# PX4FMUv2_4_6_4.net
KiCad netlist of a schematic drawn in Altium Designer
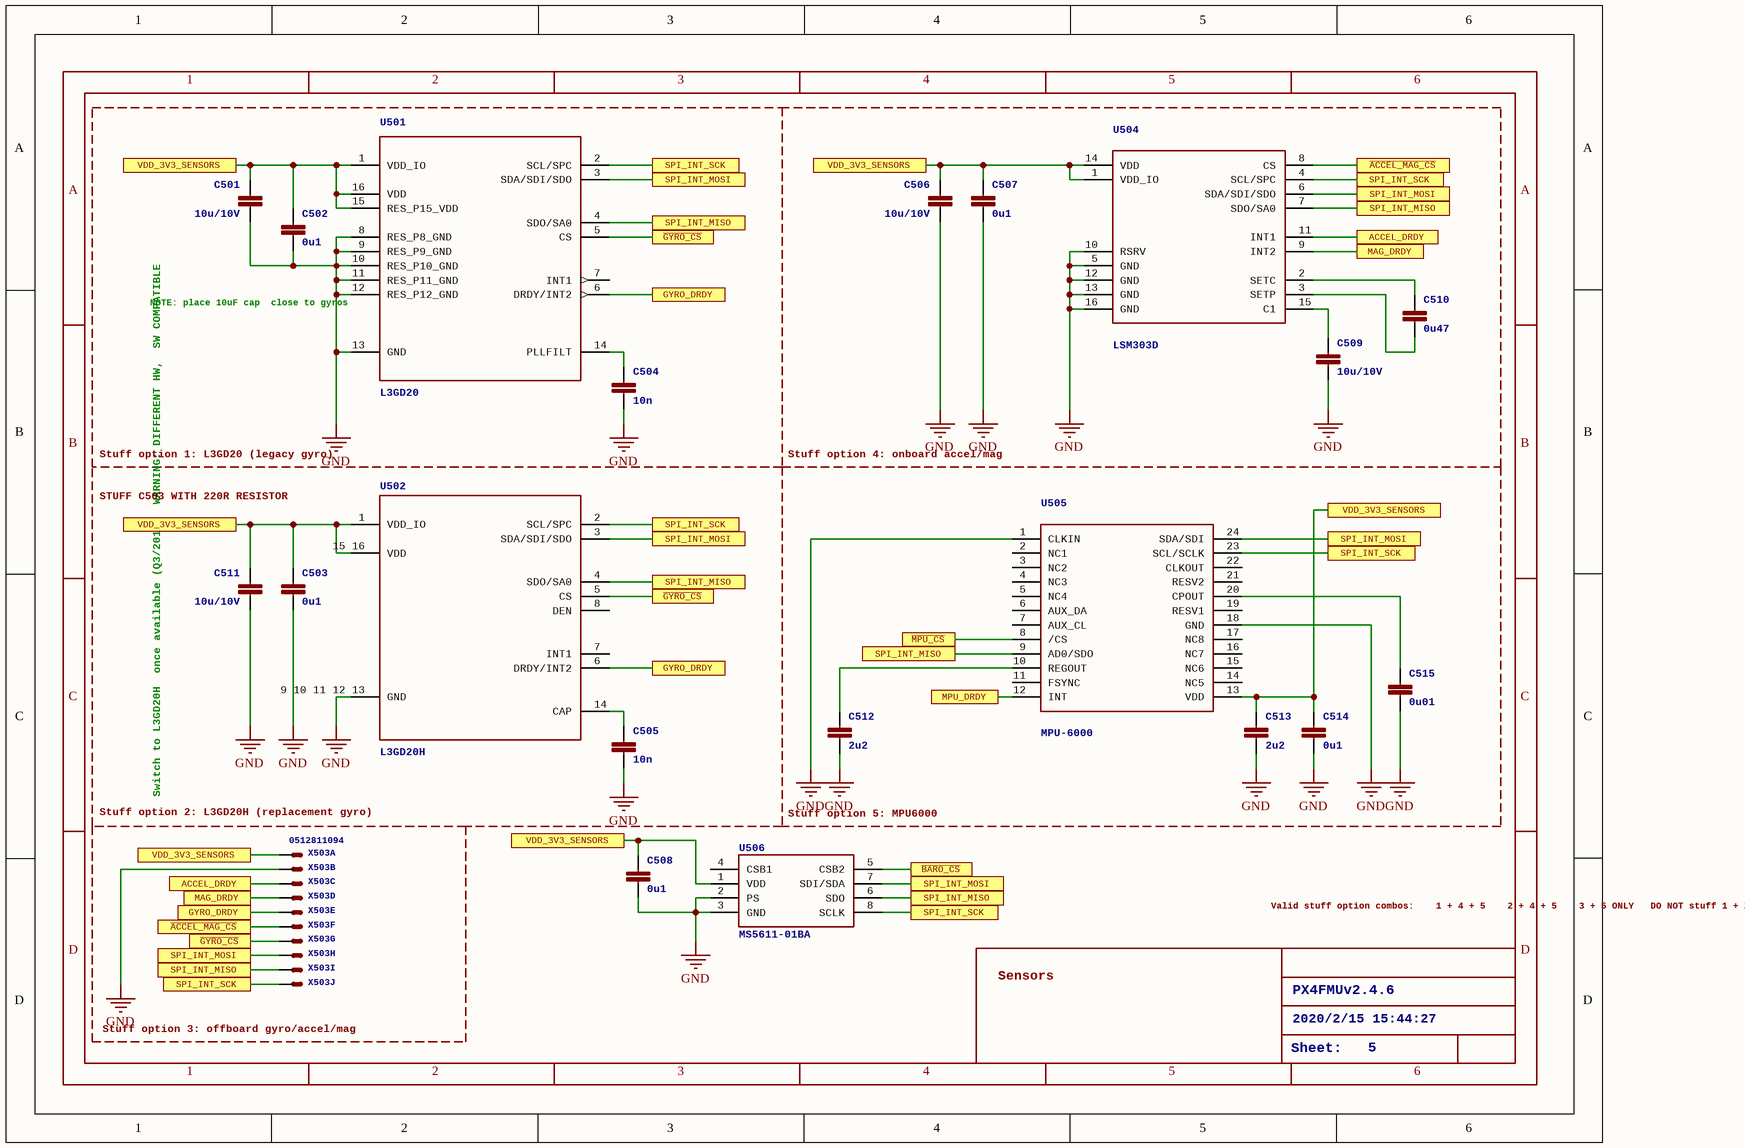
[diagram p0: PX4FMUv2.4.6_4.SchDoc]

(export (version "E")
  (design (tool "Eeschema 10.0.6"))
  (components
    (comp (ref "C501")
      (value "10u/10V")
      (footprint "0805-CAP")
      (description "CapacitorStandard 0603 ceramic capacitor, and 0.1\" leaded capacitor.")
      (fields (field (name "PARTNO") "CC0805ZKY5V6BB106"))
      (libsource (lib "pixhawk2") (part "CAP0805"))
    )
    (comp (ref "C502")
      (value "0u1")
      (footprint "0402-CAP")
      (description "CapacitorStandard 0603 ceramic capacitor, and 0.1\" leaded capacitor.")
      (fields (field (name "PARTNO") "CC0402ZRY5V7BB104"))
      (libsource (lib "pixhawk2") (part "CAP0402"))
    )
    (comp (ref "C503")
      (value "0u1")
      (footprint "0402-CAP")
      (description "CapacitorStandard 0603 ceramic capacitor, and 0.1\" leaded capacitor.")
      (fields (field (name "PARTNO") "CC0402ZRY5V7BB104"))
      (libsource (lib "pixhawk2") (part "CAP0402"))
    )
    (comp (ref "C504")
      (value "10n")
      (footprint "0402-CAP")
      (description "CapacitorStandard 0603 ceramic capacitor, and 0.1\" leaded capacitor.")
      (fields (field (name "PARTNO") "CC0402KRX7R7BB103"))
      (libsource (lib "pixhawk2") (part "CAP0402"))
    )
    (comp (ref "C505")
      (value "10n")
      (footprint "0402-CAP")
      (description "CapacitorStandard 0603 ceramic capacitor, and 0.1\" leaded capacitor.")
      (fields (field (name "PARTNO") "CC0402KRX7R7BB103"))
      (libsource (lib "pixhawk2") (part "CAP0402"))
    )
    (comp (ref "C506")
      (value "10u/10V")
      (footprint "0805-CAP")
      (description "CapacitorStandard 0603 ceramic capacitor, and 0.1\" leaded capacitor.")
      (fields (field (name "PARTNO") "CC0805ZKY5V6BB106"))
      (libsource (lib "pixhawk2") (part "CAP0805"))
    )
    (comp (ref "C507")
      (value "0u1")
      (footprint "0402-CAP")
      (description "CapacitorStandard 0603 ceramic capacitor, and 0.1\" leaded capacitor.")
      (fields (field (name "PARTNO") "CC0402ZRY5V7BB104"))
      (libsource (lib "pixhawk2") (part "CAP0402"))
    )
    (comp (ref "C508")
      (value "0u1")
      (footprint "0402-CAP")
      (description "CapacitorStandard 0603 ceramic capacitor, and 0.1\" leaded capacitor.")
      (fields (field (name "PARTNO") "CC0402ZRY5V7BB104"))
      (libsource (lib "pixhawk2") (part "CAP0402"))
    )
    (comp (ref "C509")
      (value "10u/10V")
      (footprint "0805-CAP")
      (description "CapacitorStandard 0603 ceramic capacitor, and 0.1\" leaded capacitor.")
      (fields (field (name "PARTNO") "CC0805ZKY5V6BB106"))
      (libsource (lib "") (part "CAP0805_1"))
    )
    (comp (ref "C510")
      (value "0u47")
      (footprint "0402-CAP")
      (description "CapacitorStandard 0603 ceramic capacitor, and 0.1\" leaded capacitor.")
      (fields (field (name "PARTNO") "C1005X5R1C474K050BC"))
      (libsource (lib "pixhawk2") (part "CAP0402"))
    )
    (comp (ref "C511")
      (value "10u/10V")
      (footprint "0805-CAP")
      (description "CapacitorStandard 0603 ceramic capacitor, and 0.1\" leaded capacitor.")
      (fields (field (name "PARTNO") "CC0805ZKY5V6BB106"))
      (libsource (lib "pixhawk2") (part "CAP0805"))
    )
    (comp (ref "C512")
      (value "2u2")
      (footprint "0603-CAP")
      (description "CapacitorStandard 0603 ceramic capacitor, and 0.1\" leaded capacitor.")
      (fields (field (name "PARTNO") "C1608X6S1C225K080AC"))
      (libsource (lib "pixhawk2") (part "CAP0603"))
    )
    (comp (ref "C513")
      (value "2u2")
      (footprint "0603-CAP")
      (description "CapacitorStandard 0603 ceramic capacitor, and 0.1\" leaded capacitor.")
      (fields (field (name "PARTNO") "C1608X6S1C225K080AC"))
      (libsource (lib "pixhawk2") (part "CAP0603"))
    )
    (comp (ref "C514")
      (value "0u1")
      (footprint "0402-CAP")
      (description "CapacitorStandard 0603 ceramic capacitor, and 0.1\" leaded capacitor.")
      (fields (field (name "PARTNO") "CC0402ZRY5V7BB104"))
      (libsource (lib "pixhawk2") (part "CAP0402"))
    )
    (comp (ref "C515")
      (value "0u01")
      (footprint "0603-CAP")
      (description "CapacitorStandard 0603 ceramic capacitor, and 0.1\" leaded capacitor.")
      (fields (field (name "PARTNO") "06033C103JAT2A"))
      (libsource (lib "pixhawk2") (part "CAP0603"))
    )
    (comp (ref "U501")
      (value "L3GD20")
      (footprint "L3G4200DH-MAN")
      (libsource (lib "pixhawk2") (part "L3G4200DH-LL"))
    )
    (comp (ref "U502")
      (value "L3GD20H")
      (footprint "LGA-16L")
      (description "L3GD20H MEMS motion sensor: 3-axis digital output gyroscope")
      (libsource (lib "pixhawk2") (part "L3GD20H"))
    )
    (comp (ref "U504")
      (value "LSM303D")
      (footprint "LGA-16L")
      (description "LSM303D Ultra compact high performance e-compass: 3D accelerometer and 3D magnetometer module")
      (libsource (lib "pixhawk2") (part "LSM303D"))
    )
    (comp (ref "U505") (value "MPU-6000") (footprint "QFN-24") (libsource (lib "pixhawk2") (part "MPU-6000")))
    (comp (ref "U506")
      (value "MS5611-01BA")
      (footprint "MS5611-01BA")
      (libsource (lib "pixhawk2") (part "MS5611-01BA"))
    )
    (comp (ref "X503")
      (value "0512811094")
      (footprint "51281-1094")
      (description "10-pin FPC connector for PX4 sensor board")
      (fields (field (name "PARTNO") "0781191109"))
      (libsource (lib "pixhawk2") (part "CONN_FPC_10RA"))
    )
  )
  (nets
    (net (code "1") (name "/ACCEL_DRDY") (class "Default")
      (node (ref "U504") (pin "11") (pinfunction "INT1_11") (pintype "passive"))
      (node (ref "X503") (pin "3") (pinfunction "S_3") (pintype "passive"))
    )
    (net (code "2") (name "/GYRO_DRDY") (class "Default")
      (node (ref "U501") (pin "6") (pinfunction "DRDY/INT2_6") (pintype "output"))
      (node (ref "U502") (pin "6") (pinfunction "DRDY/INT2_6") (pintype "passive"))
      (node (ref "X503") (pin "5") (pinfunction "S_5") (pintype "passive"))
    )
    (net (code "3") (name "/MAG_DRDY") (class "Default")
      (node (ref "U504") (pin "9") (pinfunction "INT2_9") (pintype "passive"))
      (node (ref "X503") (pin "4") (pinfunction "S_4") (pintype "passive"))
    )
    (net (code "4") (name "/MPU_DRDY") (class "Default")
      (node (ref "U505") (pin "12") (pinfunction "INT_12") (pintype "passive"))
    )
    (net (code "5") (name "/SPI_INT_MISO") (class "Default")
      (node (ref "U501") (pin "4") (pinfunction "SDO/SA0_4") (pintype "passive"))
      (node (ref "U502") (pin "4") (pinfunction "SDO/SA0_4") (pintype "passive"))
      (node (ref "U504") (pin "7") (pinfunction "SDO/SA0_7") (pintype "passive"))
      (node (ref "U505") (pin "9") (pinfunction "AD0/SDO_9") (pintype "passive"))
      (node (ref "U506") (pin "6") (pinfunction "SDO_6") (pintype "passive"))
      (node (ref "X503") (pin "9") (pinfunction "S_9") (pintype "passive"))
    )
    (net (code "6") (name "/SPI_INT_MOSI") (class "Default")
      (node (ref "U501") (pin "3") (pinfunction "SDA/SDI/SDO_3") (pintype "passive"))
      (node (ref "U502") (pin "3") (pinfunction "SDA/SDI/SDO_3") (pintype "passive"))
      (node (ref "U504") (pin "6") (pinfunction "SDA/SDI/SDO_6") (pintype "passive"))
      (node (ref "U505") (pin "24") (pinfunction "SDA/SDI_24") (pintype "passive"))
      (node (ref "U506") (pin "7") (pinfunction "SDI/SDA_7") (pintype "passive"))
      (node (ref "X503") (pin "8") (pinfunction "S_8") (pintype "passive"))
    )
    (net (code "7") (name "/SPI_INT_SCK") (class "Default")
      (node (ref "U501") (pin "2") (pinfunction "SCL/SPC_2") (pintype "passive"))
      (node (ref "U502") (pin "2") (pinfunction "SCL/SPC_2") (pintype "passive"))
      (node (ref "U504") (pin "4") (pinfunction "SCL/SPC_4") (pintype "passive"))
      (node (ref "U505") (pin "23") (pinfunction "SCL/SCLK_23") (pintype "passive"))
      (node (ref "U506") (pin "8") (pinfunction "SCLK_8") (pintype "passive"))
      (node (ref "X503") (pin "10") (pinfunction "S_10") (pintype "passive"))
    )
    (net (code "8") (name "/VDD_3V3_SENSORS") (class "Default")
      (node (ref "C501") (pin "P$1") (pinfunction "1_P$1") (pintype "passive"))
      (node (ref "C502") (pin "P$1") (pinfunction "1_P$1") (pintype "passive"))
      (node (ref "C503") (pin "P$1") (pinfunction "1_P$1") (pintype "passive"))
      (node (ref "C506") (pin "P$1") (pinfunction "1_P$1") (pintype "passive"))
      (node (ref "C507") (pin "P$1") (pinfunction "1_P$1") (pintype "passive"))
      (node (ref "C508") (pin "P$1") (pinfunction "1_P$1") (pintype "passive"))
      (node (ref "C511") (pin "P$1") (pinfunction "1_P$1") (pintype "passive"))
      (node (ref "C513") (pin "P$1") (pinfunction "1_P$1") (pintype "passive"))
      (node (ref "C514") (pin "P$1") (pinfunction "1_P$1") (pintype "passive"))
      (node (ref "U501") (pin "1") (pinfunction "VDD_IO_1") (pintype "passive"))
      (node (ref "U501") (pin "15") (pinfunction "RES_P15_VDD_15") (pintype "passive"))
      (node (ref "U501") (pin "16") (pinfunction "VDD_16") (pintype "passive"))
      (node (ref "U502") (pin "1") (pinfunction "VDD_IO_1") (pintype "passive"))
      (node (ref "U502") (pin "15_16") (pinfunction "VDD_15_16") (pintype "passive"))
      (node (ref "U504") (pin "1") (pinfunction "VDD_IO_1") (pintype "passive"))
      (node (ref "U504") (pin "14") (pinfunction "VDD_14") (pintype "passive"))
      (node (ref "U505") (pin "13") (pinfunction "VDD_13") (pintype "passive"))
      (node (ref "U506") (pin "1") (pinfunction "VDD_1") (pintype "passive"))
      (node (ref "X503") (pin "1") (pinfunction "S_1") (pintype "passive"))
    )
    (net (code "9") (name "/~{ACCEL_MAG_CS}") (class "Default")
      (node (ref "U504") (pin "8") (pinfunction "CS_8") (pintype "passive"))
      (node (ref "X503") (pin "6") (pinfunction "S_6") (pintype "passive"))
    )
    (net (code "10") (name "/~{BARO_CS}") (class "Default")
      (node (ref "U506") (pin "5") (pinfunction "CSB2_5") (pintype "passive"))
    )
    (net (code "11") (name "/~{GYRO_CS}") (class "Default")
      (node (ref "U501") (pin "5") (pinfunction "CS_5") (pintype "passive"))
      (node (ref "U502") (pin "5") (pinfunction "CS_5") (pintype "passive"))
      (node (ref "X503") (pin "7") (pinfunction "S_7") (pintype "passive"))
    )
    (net (code "12") (name "/~{MPU_CS}") (class "Default")
      (node (ref "U505") (pin "8") (pinfunction "/CS_8") (pintype "passive"))
    )
    (net (code "13") (name "GND") (class "Default")
      (node (ref "C501") (pin "P$2") (pinfunction "2_P$2") (pintype "passive"))
      (node (ref "C502") (pin "P$2") (pinfunction "2_P$2") (pintype "passive"))
      (node (ref "C503") (pin "P$2") (pinfunction "2_P$2") (pintype "passive"))
      (node (ref "C504") (pin "P$2") (pinfunction "2_P$2") (pintype "passive"))
      (node (ref "C505") (pin "P$2") (pinfunction "2_P$2") (pintype "passive"))
      (node (ref "C506") (pin "P$2") (pinfunction "2_P$2") (pintype "passive"))
      (node (ref "C507") (pin "P$2") (pinfunction "2_P$2") (pintype "passive"))
      (node (ref "C508") (pin "P$2") (pinfunction "2_P$2") (pintype "passive"))
      (node (ref "C509") (pin "P$2") (pinfunction "2_P$2") (pintype "passive"))
      (node (ref "C511") (pin "P$2") (pinfunction "2_P$2") (pintype "passive"))
      (node (ref "C512") (pin "P$2") (pinfunction "2_P$2") (pintype "passive"))
      (node (ref "C513") (pin "P$2") (pinfunction "2_P$2") (pintype "passive"))
      (node (ref "C514") (pin "P$2") (pinfunction "2_P$2") (pintype "passive"))
      (node (ref "C515") (pin "P$2") (pinfunction "2_P$2") (pintype "passive"))
      (node (ref "U501") (pin "10") (pinfunction "RES_P10_GND_10") (pintype "passive"))
      (node (ref "U501") (pin "11") (pinfunction "RES_P11_GND_11") (pintype "passive"))
      (node (ref "U501") (pin "12") (pinfunction "RES_P12_GND_12") (pintype "passive"))
      (node (ref "U501") (pin "13") (pinfunction "GND_13") (pintype "passive"))
      (node (ref "U501") (pin "8") (pinfunction "RES_P8_GND_8") (pintype "passive"))
      (node (ref "U501") (pin "9") (pinfunction "RES_P9_GND_9") (pintype "passive"))
      (node (ref "U502") (pin "9_10_11_12_13") (pinfunction "GND_9_10_11_12_13") (pintype "passive"))
      (node (ref "U504") (pin "10") (pinfunction "RSRV_10") (pintype "passive"))
      (node (ref "U504") (pin "12") (pinfunction "GND_12") (pintype "passive"))
      (node (ref "U504") (pin "13") (pinfunction "GND_13") (pintype "passive"))
      (node (ref "U504") (pin "16") (pinfunction "GND_16") (pintype "passive"))
      (node (ref "U504") (pin "5") (pinfunction "GND_5") (pintype "passive"))
      (node (ref "U505") (pin "1") (pinfunction "CLKIN_1") (pintype "passive"))
      (node (ref "U505") (pin "18") (pinfunction "GND_18") (pintype "passive"))
      (node (ref "U506") (pin "2") (pinfunction "PS_2") (pintype "passive"))
      (node (ref "U506") (pin "3") (pinfunction "GND_3") (pintype "passive"))
      (node (ref "X503") (pin "2") (pinfunction "S_2") (pintype "passive"))
    )
    (net (code "14") (name "Net-(C504-1)") (class "Default")
      (node (ref "C504") (pin "P$1") (pinfunction "1_P$1") (pintype "passive"))
      (node (ref "U501") (pin "14") (pinfunction "PLLFILT_14") (pintype "passive"))
    )
    (net (code "15") (name "Net-(C505-1)") (class "Default")
      (node (ref "C505") (pin "P$1") (pinfunction "1_P$1") (pintype "passive"))
      (node (ref "U502") (pin "14") (pinfunction "CAP_14") (pintype "passive"))
    )
    (net (code "16") (name "Net-(C509-1)") (class "Default")
      (node (ref "C509") (pin "P$1") (pinfunction "1_P$1") (pintype "passive"))
      (node (ref "U504") (pin "15") (pinfunction "C1_15") (pintype "passive"))
    )
    (net (code "17") (name "Net-(C510-1)") (class "Default")
      (node (ref "C510") (pin "P$1") (pinfunction "1_P$1") (pintype "passive"))
      (node (ref "U504") (pin "2") (pinfunction "SETC_2") (pintype "passive"))
    )
    (net (code "18") (name "Net-(C510-2)") (class "Default")
      (node (ref "C510") (pin "P$2") (pinfunction "2_P$2") (pintype "passive"))
      (node (ref "U504") (pin "3") (pinfunction "SETP_3") (pintype "passive"))
    )
    (net (code "19") (name "Net-(C512-1)") (class "Default")
      (node (ref "C512") (pin "P$1") (pinfunction "1_P$1") (pintype "passive"))
      (node (ref "U505") (pin "10") (pinfunction "REGOUT_10") (pintype "passive"))
    )
    (net (code "20") (name "Net-(C515-1)") (class "Default")
      (node (ref "C515") (pin "P$1") (pinfunction "1_P$1") (pintype "passive"))
      (node (ref "U505") (pin "20") (pinfunction "CPOUT_20") (pintype "passive"))
    )
    (net (code "21") (name "unconnected-(U501-INT1-Pad7)") (class "Default")
      (node (ref "U501") (pin "7") (pinfunction "INT1_7") (pintype "output"))
    )
    (net (code "22") (name "unconnected-(U502-DEN-Pad8)") (class "Default")
      (node (ref "U502") (pin "8") (pinfunction "DEN_8") (pintype "passive"))
    )
    (net (code "23") (name "unconnected-(U502-INT1-Pad7)") (class "Default")
      (node (ref "U502") (pin "7") (pinfunction "INT1_7") (pintype "passive"))
    )
    (net (code "24") (name "unconnected-(U505-AUX_CL-Pad7)") (class "Default")
      (node (ref "U505") (pin "7") (pinfunction "AUX_CL_7") (pintype "passive"))
    )
    (net (code "25") (name "unconnected-(U505-AUX_DA-Pad6)") (class "Default")
      (node (ref "U505") (pin "6") (pinfunction "AUX_DA_6") (pintype "passive"))
    )
    (net (code "26") (name "unconnected-(U505-CLKOUT-Pad22)") (class "Default")
      (node (ref "U505") (pin "22") (pinfunction "CLKOUT_22") (pintype "passive"))
    )
    (net (code "27") (name "unconnected-(U505-FSYNC-Pad11)") (class "Default")
      (node (ref "U505") (pin "11") (pinfunction "FSYNC_11") (pintype "passive"))
    )
    (net (code "28") (name "unconnected-(U505-NC1-Pad2)") (class "Default")
      (node (ref "U505") (pin "2") (pinfunction "NC1_2") (pintype "passive"))
    )
    (net (code "29") (name "unconnected-(U505-NC2-Pad3)") (class "Default")
      (node (ref "U505") (pin "3") (pinfunction "NC2_3") (pintype "passive"))
    )
    (net (code "30") (name "unconnected-(U505-NC3-Pad4)") (class "Default")
      (node (ref "U505") (pin "4") (pinfunction "NC3_4") (pintype "passive"))
    )
    (net (code "31") (name "unconnected-(U505-NC4-Pad5)") (class "Default")
      (node (ref "U505") (pin "5") (pinfunction "NC4_5") (pintype "passive"))
    )
    (net (code "32") (name "unconnected-(U505-NC5-Pad14)") (class "Default")
      (node (ref "U505") (pin "14") (pinfunction "NC5_14") (pintype "passive"))
    )
    (net (code "33") (name "unconnected-(U505-NC6-Pad15)") (class "Default")
      (node (ref "U505") (pin "15") (pinfunction "NC6_15") (pintype "passive"))
    )
    (net (code "34") (name "unconnected-(U505-NC7-Pad16)") (class "Default")
      (node (ref "U505") (pin "16") (pinfunction "NC7_16") (pintype "passive"))
    )
    (net (code "35") (name "unconnected-(U505-NC8-Pad17)") (class "Default")
      (node (ref "U505") (pin "17") (pinfunction "NC8_17") (pintype "passive"))
    )
    (net (code "36") (name "unconnected-(U505-RESV1-Pad19)") (class "Default")
      (node (ref "U505") (pin "19") (pinfunction "RESV1_19") (pintype "passive"))
    )
    (net (code "37") (name "unconnected-(U505-RESV2-Pad21)") (class "Default")
      (node (ref "U505") (pin "21") (pinfunction "RESV2_21") (pintype "passive"))
    )
    (net (code "38") (name "unconnected-(U506-CSB1-Pad4)") (class "Default")
      (node (ref "U506") (pin "4") (pinfunction "CSB1_4") (pintype "passive"))
    )
  )
)
